# Feedback.net
KiCad netlist of a schematic drawn in Altium Designer
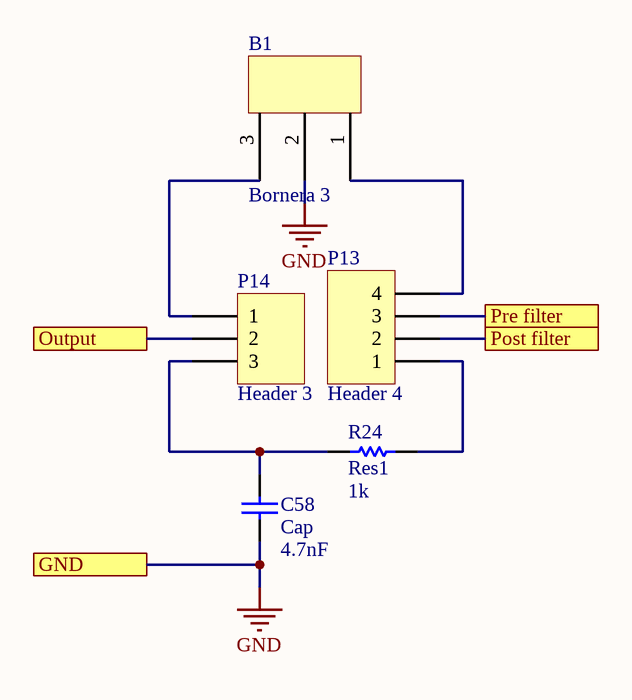
[diagram p0: Feedback.SchDoc]

(export (version "E")
  (design (tool "Eeschema 10.0.6"))
  (components
    (comp (ref "B1")
      (value "Bornera 3")
      (footprint "bornera 3")
      (libsource (lib "Userlib") (part "Bornera 3"))
    )
    (comp (ref "C58")
      (value "Cap")
      (footprint "CAP DISCO 200mil")
      (description "Capacitor")
      (fields (field (name "ALTIUM_VALUE") "4.7nF") (field (name "PUBLISHER") "Altium Limited"))
      (libsource (lib "Miscellaneous Devices") (part "Cap"))
    )
    (comp (ref "P13")
      (value "Header 4")
      (footprint "HDR1X4")
      (description "Header, 4-Pin")
      (fields (field (name "PUBLISHER") "Altium Limited"))
      (libsource (lib "Miscellaneous Connectors") (part "Header 4"))
    )
    (comp (ref "P14")
      (value "Header 3")
      (footprint "HDR1X3")
      (description "Header, 3-Pin")
      (fields (field (name "PUBLISHER") "Altium Limited"))
      (libsource (lib "Miscellaneous Connectors") (part "Header 3"))
    )
    (comp (ref "R24")
      (value "Res1")
      (footprint "1206 resistor")
      (description "Resistor")
      (fields (field (name "ALTIUM_VALUE") "1k") (field (name "PUBLISHER") "Altium Limited"))
      (libsource (lib "Miscellaneous Devices") (part "Res1"))
    )
  )
  (nets
    (net (code "1") (name "/Output") (class "Default")
      (node (ref "P14") (pin "2") (pinfunction "2_2") (pintype "passive"))
    )
    (net (code "2") (name "/Post filter") (class "Default")
      (node (ref "P13") (pin "2") (pinfunction "2_2") (pintype "passive"))
    )
    (net (code "3") (name "/Pre filter") (class "Default")
      (node (ref "P13") (pin "3") (pinfunction "3_3") (pintype "passive"))
    )
    (net (code "4") (name "GND") (class "Default")
      (node (ref "B1") (pin "2") (pinfunction "L_2") (pintype "passive"))
      (node (ref "C58") (pin "1") (pinfunction "1_1") (pintype "passive"))
    )
    (net (code "5") (name "Net-(B1-L-Pad1)") (class "Default")
      (node (ref "B1") (pin "1") (pinfunction "L_1") (pintype "passive"))
      (node (ref "P13") (pin "4") (pinfunction "4_4") (pintype "passive"))
    )
    (net (code "6") (name "Net-(B1-L-Pad3)") (class "Default")
      (node (ref "B1") (pin "3") (pinfunction "L_3") (pintype "passive"))
      (node (ref "P14") (pin "1") (pinfunction "1_1") (pintype "passive"))
    )
    (net (code "7") (name "Net-(C58-Pad2)") (class "Default")
      (node (ref "C58") (pin "2") (pinfunction "2_2") (pintype "passive"))
      (node (ref "P14") (pin "3") (pinfunction "3_3") (pintype "passive"))
      (node (ref "R24") (pin "2") (pinfunction "2_2") (pintype "passive"))
    )
    (net (code "8") (name "Net-(P13-Pad1)") (class "Default")
      (node (ref "P13") (pin "1") (pinfunction "1_1") (pintype "passive"))
      (node (ref "R24") (pin "1") (pinfunction "1_1") (pintype "passive"))
    )
  )
)
